# tvac_systems_interface.net
KiCad netlist of a schematic drawn in Altium Designer
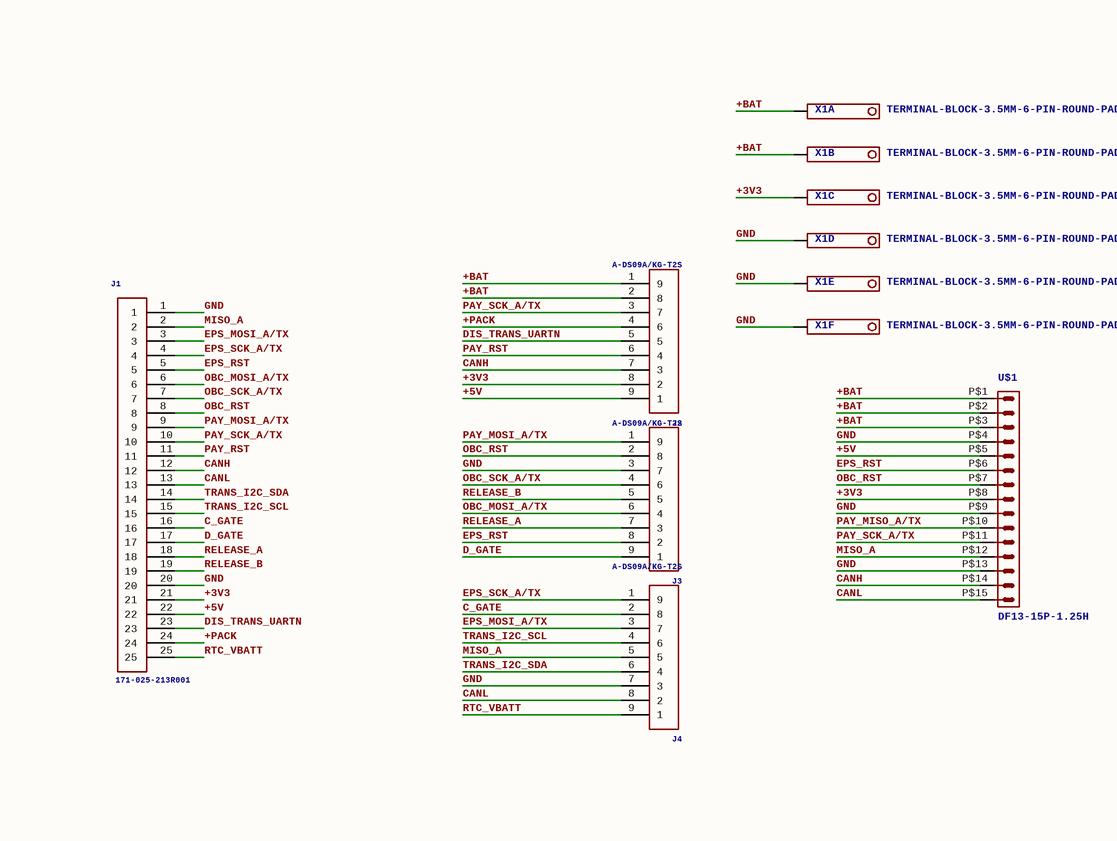
[diagram p0: tvac_systems_interface.SchDoc]

(export (version "E")
  (design (tool "Eeschema 10.0.6"))
  (components
    (comp (ref "J1")
      (value "171-025-213R001")
      (footprint "171-025-213R001")
      (description "CONN D-SUB RCPT 25P PNL MNT SLDR    Manufacturer's datasheet")
      (fields
        (field (name "DIGIKEY_PART_NO") "4225FE-ND")
        (field (name "MANUFACTURER") "NorComp Inc.")
        (field (name "CREATED_BY") "PCBLayout.com")
      )
      (libsource (lib "D-Sub Connectors") (part "171-025-213R001"))
    )
    (comp (ref "J2")
      (value "A-DS09A/KG-T2S")
      (footprint "A-DS09A/KG-T2S")
      (description "CONN D-SUB PLUG 9POS R/A SOLDER    Manufacturer's datasheet")
      (fields
        (field (name "DIGI_KEY_PART_NUMBER") "AE10968-ND")
        (field (name "MANUFACTURER") "Assmann WSW Components")
        (field (name "CREATEDBY") "PCBLayout.com")
      )
      (libsource (lib "D-Sub Connectors") (part "A-DS09A/KG-T2S"))
    )
    (comp (ref "J3")
      (value "A-DS09A/KG-T2S")
      (footprint "A-DS09A/KG-T2S")
      (description "CONN D-SUB PLUG 9POS R/A SOLDER    Manufacturer's datasheet")
      (fields
        (field (name "DIGI_KEY_PART_NUMBER") "AE10968-ND")
        (field (name "MANUFACTURER") "Assmann WSW Components")
        (field (name "CREATEDBY") "PCBLayout.com")
      )
      (libsource (lib "D-Sub Connectors") (part "A-DS09A/KG-T2S"))
    )
    (comp (ref "J4")
      (value "A-DS09A/KG-T2S")
      (footprint "A-DS09A/KG-T2S")
      (description "CONN D-SUB PLUG 9POS R/A SOLDER    Manufacturer's datasheet")
      (fields
        (field (name "DIGI_KEY_PART_NUMBER") "AE10968-ND")
        (field (name "MANUFACTURER") "Assmann WSW Components")
        (field (name "CREATEDBY") "PCBLayout.com")
      )
      (libsource (lib "D-Sub Connectors") (part "A-DS09A/KG-T2S"))
    )
    (comp (ref "U$1")
      (value "DF13-15P-1.25H")
      (footprint "DF13A-15P-1.25H")
      (description "DF13-15P 1.25mm Pitch Miniature Crimping Connector.")
      (fields (field (name "LIBRARYNAME") "con-hirose-df13"))
      (libsource (lib "con-hirose-df13") (part "DF13-15P-1.25H"))
    )
    (comp (ref "X1")
      (value "TERMINAL-BLOCK-3.5MM-6-PIN-ROUND-PAD")
      (footprint "TERMINAL-BLOCK-6-PIN-3.5MM-ROUND-PAD")
      (libsource (lib "Rembrandt Electronics - Terminal Block 3-5mm v1-0") (part "TERMINAL-BLOCK-3.5MM-6-PIN-ROUND-PAD"))
    )
  )
  (nets
    (net (code "1") (name "/+3V3") (class "Default")
      (node (ref "J1") (pin "21") (pinfunction "21_21") (pintype "passive"))
      (node (ref "J2") (pin "8") (pinfunction "2_8") (pintype "passive"))
      (node (ref "U$1") (pin "P$8") (pinfunction "8_P$8") (pintype "passive"))
      (node (ref "X1") (pin "3") (pinfunction "K_3") (pintype "passive"))
    )
    (net (code "2") (name "/+5V") (class "Default")
      (node (ref "J1") (pin "22") (pinfunction "22_22") (pintype "passive"))
      (node (ref "J2") (pin "9") (pinfunction "1_9") (pintype "passive"))
      (node (ref "U$1") (pin "P$5") (pinfunction "5_P$5") (pintype "passive"))
    )
    (net (code "3") (name "/+BAT") (class "Default")
      (node (ref "J2") (pin "1") (pinfunction "9_1") (pintype "passive"))
      (node (ref "J2") (pin "2") (pinfunction "8_2") (pintype "passive"))
      (node (ref "U$1") (pin "P$1") (pinfunction "1_P$1") (pintype "passive"))
      (node (ref "U$1") (pin "P$2") (pinfunction "2_P$2") (pintype "passive"))
      (node (ref "U$1") (pin "P$3") (pinfunction "3_P$3") (pintype "passive"))
      (node (ref "X1") (pin "1") (pinfunction "K_1") (pintype "passive"))
      (node (ref "X1") (pin "2") (pinfunction "K_2") (pintype "passive"))
    )
    (net (code "4") (name "/+PACK") (class "Default")
      (node (ref "J1") (pin "24") (pinfunction "24_24") (pintype "passive"))
      (node (ref "J2") (pin "4") (pinfunction "6_4") (pintype "passive"))
    )
    (net (code "5") (name "/CANH") (class "Default")
      (node (ref "J1") (pin "12") (pinfunction "12_12") (pintype "passive"))
      (node (ref "J2") (pin "7") (pinfunction "3_7") (pintype "passive"))
      (node (ref "U$1") (pin "P$14") (pinfunction "14_P$14") (pintype "passive"))
    )
    (net (code "6") (name "/CANL") (class "Default")
      (node (ref "J1") (pin "13") (pinfunction "13_13") (pintype "passive"))
      (node (ref "J4") (pin "8") (pinfunction "2_8") (pintype "passive"))
      (node (ref "U$1") (pin "P$15") (pinfunction "15_P$15") (pintype "passive"))
    )
    (net (code "7") (name "/C_GATE") (class "Default")
      (node (ref "J1") (pin "16") (pinfunction "16_16") (pintype "passive"))
      (node (ref "J4") (pin "2") (pinfunction "8_2") (pintype "passive"))
    )
    (net (code "8") (name "/DIS_TRANS_UARTN") (class "Default")
      (node (ref "J1") (pin "23") (pinfunction "23_23") (pintype "passive"))
      (node (ref "J2") (pin "5") (pinfunction "5_5") (pintype "passive"))
    )
    (net (code "9") (name "/D_GATE") (class "Default")
      (node (ref "J1") (pin "17") (pinfunction "17_17") (pintype "passive"))
      (node (ref "J3") (pin "9") (pinfunction "1_9") (pintype "passive"))
    )
    (net (code "10") (name "/EPS_MOSI_A{slash}TX") (class "Default")
      (node (ref "J1") (pin "3") (pinfunction "3_3") (pintype "passive"))
      (node (ref "J4") (pin "3") (pinfunction "7_3") (pintype "passive"))
    )
    (net (code "11") (name "/EPS_RST") (class "Default")
      (node (ref "J1") (pin "5") (pinfunction "5_5") (pintype "passive"))
      (node (ref "J3") (pin "8") (pinfunction "2_8") (pintype "passive"))
      (node (ref "U$1") (pin "P$6") (pinfunction "6_P$6") (pintype "passive"))
    )
    (net (code "12") (name "/EPS_SCK_A{slash}TX") (class "Default")
      (node (ref "J1") (pin "4") (pinfunction "4_4") (pintype "passive"))
      (node (ref "J4") (pin "1") (pinfunction "9_1") (pintype "passive"))
    )
    (net (code "13") (name "/GND") (class "Default")
      (node (ref "J1") (pin "1") (pinfunction "1_1") (pintype "passive"))
      (node (ref "J1") (pin "20") (pinfunction "20_20") (pintype "passive"))
      (node (ref "J3") (pin "3") (pinfunction "7_3") (pintype "passive"))
      (node (ref "J4") (pin "7") (pinfunction "3_7") (pintype "passive"))
      (node (ref "U$1") (pin "P$13") (pinfunction "13_P$13") (pintype "passive"))
      (node (ref "U$1") (pin "P$4") (pinfunction "4_P$4") (pintype "passive"))
      (node (ref "U$1") (pin "P$9") (pinfunction "9_P$9") (pintype "passive"))
      (node (ref "X1") (pin "4") (pinfunction "K_4") (pintype "passive"))
      (node (ref "X1") (pin "5") (pinfunction "K_5") (pintype "passive"))
      (node (ref "X1") (pin "6") (pinfunction "K_6") (pintype "passive"))
    )
    (net (code "14") (name "/MISO_A") (class "Default")
      (node (ref "J1") (pin "2") (pinfunction "2_2") (pintype "passive"))
      (node (ref "J4") (pin "5") (pinfunction "5_5") (pintype "passive"))
      (node (ref "U$1") (pin "P$12") (pinfunction "12_P$12") (pintype "passive"))
    )
    (net (code "15") (name "/OBC_MOSI_A{slash}TX") (class "Default")
      (node (ref "J1") (pin "6") (pinfunction "6_6") (pintype "passive"))
      (node (ref "J3") (pin "6") (pinfunction "4_6") (pintype "passive"))
    )
    (net (code "16") (name "/OBC_RST") (class "Default")
      (node (ref "J1") (pin "8") (pinfunction "8_8") (pintype "passive"))
      (node (ref "J3") (pin "2") (pinfunction "8_2") (pintype "passive"))
      (node (ref "U$1") (pin "P$7") (pinfunction "7_P$7") (pintype "passive"))
    )
    (net (code "17") (name "/OBC_SCK_A{slash}TX") (class "Default")
      (node (ref "J1") (pin "7") (pinfunction "7_7") (pintype "passive"))
      (node (ref "J3") (pin "4") (pinfunction "6_4") (pintype "passive"))
    )
    (net (code "18") (name "/PAY_MISO_A{slash}TX") (class "Default")
      (node (ref "U$1") (pin "P$10") (pinfunction "10_P$10") (pintype "passive"))
    )
    (net (code "19") (name "/PAY_MOSI_A{slash}TX") (class "Default")
      (node (ref "J1") (pin "9") (pinfunction "9_9") (pintype "passive"))
      (node (ref "J3") (pin "1") (pinfunction "9_1") (pintype "passive"))
    )
    (net (code "20") (name "/PAY_RST") (class "Default")
      (node (ref "J1") (pin "11") (pinfunction "11_11") (pintype "passive"))
      (node (ref "J2") (pin "6") (pinfunction "4_6") (pintype "passive"))
    )
    (net (code "21") (name "/PAY_SCK_A{slash}TX") (class "Default")
      (node (ref "J1") (pin "10") (pinfunction "10_10") (pintype "passive"))
      (node (ref "J2") (pin "3") (pinfunction "7_3") (pintype "passive"))
      (node (ref "U$1") (pin "P$11") (pinfunction "11_P$11") (pintype "passive"))
    )
    (net (code "22") (name "/RELEASE_A") (class "Default")
      (node (ref "J1") (pin "18") (pinfunction "18_18") (pintype "passive"))
      (node (ref "J3") (pin "7") (pinfunction "3_7") (pintype "passive"))
    )
    (net (code "23") (name "/RELEASE_B") (class "Default")
      (node (ref "J1") (pin "19") (pinfunction "19_19") (pintype "passive"))
      (node (ref "J3") (pin "5") (pinfunction "5_5") (pintype "passive"))
    )
    (net (code "24") (name "/RTC_VBATT") (class "Default")
      (node (ref "J1") (pin "25") (pinfunction "25_25") (pintype "passive"))
      (node (ref "J4") (pin "9") (pinfunction "1_9") (pintype "passive"))
    )
    (net (code "25") (name "/TRANS_I2C_SCL") (class "Default")
      (node (ref "J1") (pin "15") (pinfunction "15_15") (pintype "passive"))
      (node (ref "J4") (pin "4") (pinfunction "6_4") (pintype "passive"))
    )
    (net (code "26") (name "/TRANS_I2C_SDA") (class "Default")
      (node (ref "J1") (pin "14") (pinfunction "14_14") (pintype "passive"))
      (node (ref "J4") (pin "6") (pinfunction "4_6") (pintype "passive"))
    )
  )
)
